# LARS.net
KiCad netlist of a schematic drawn in EAGLE
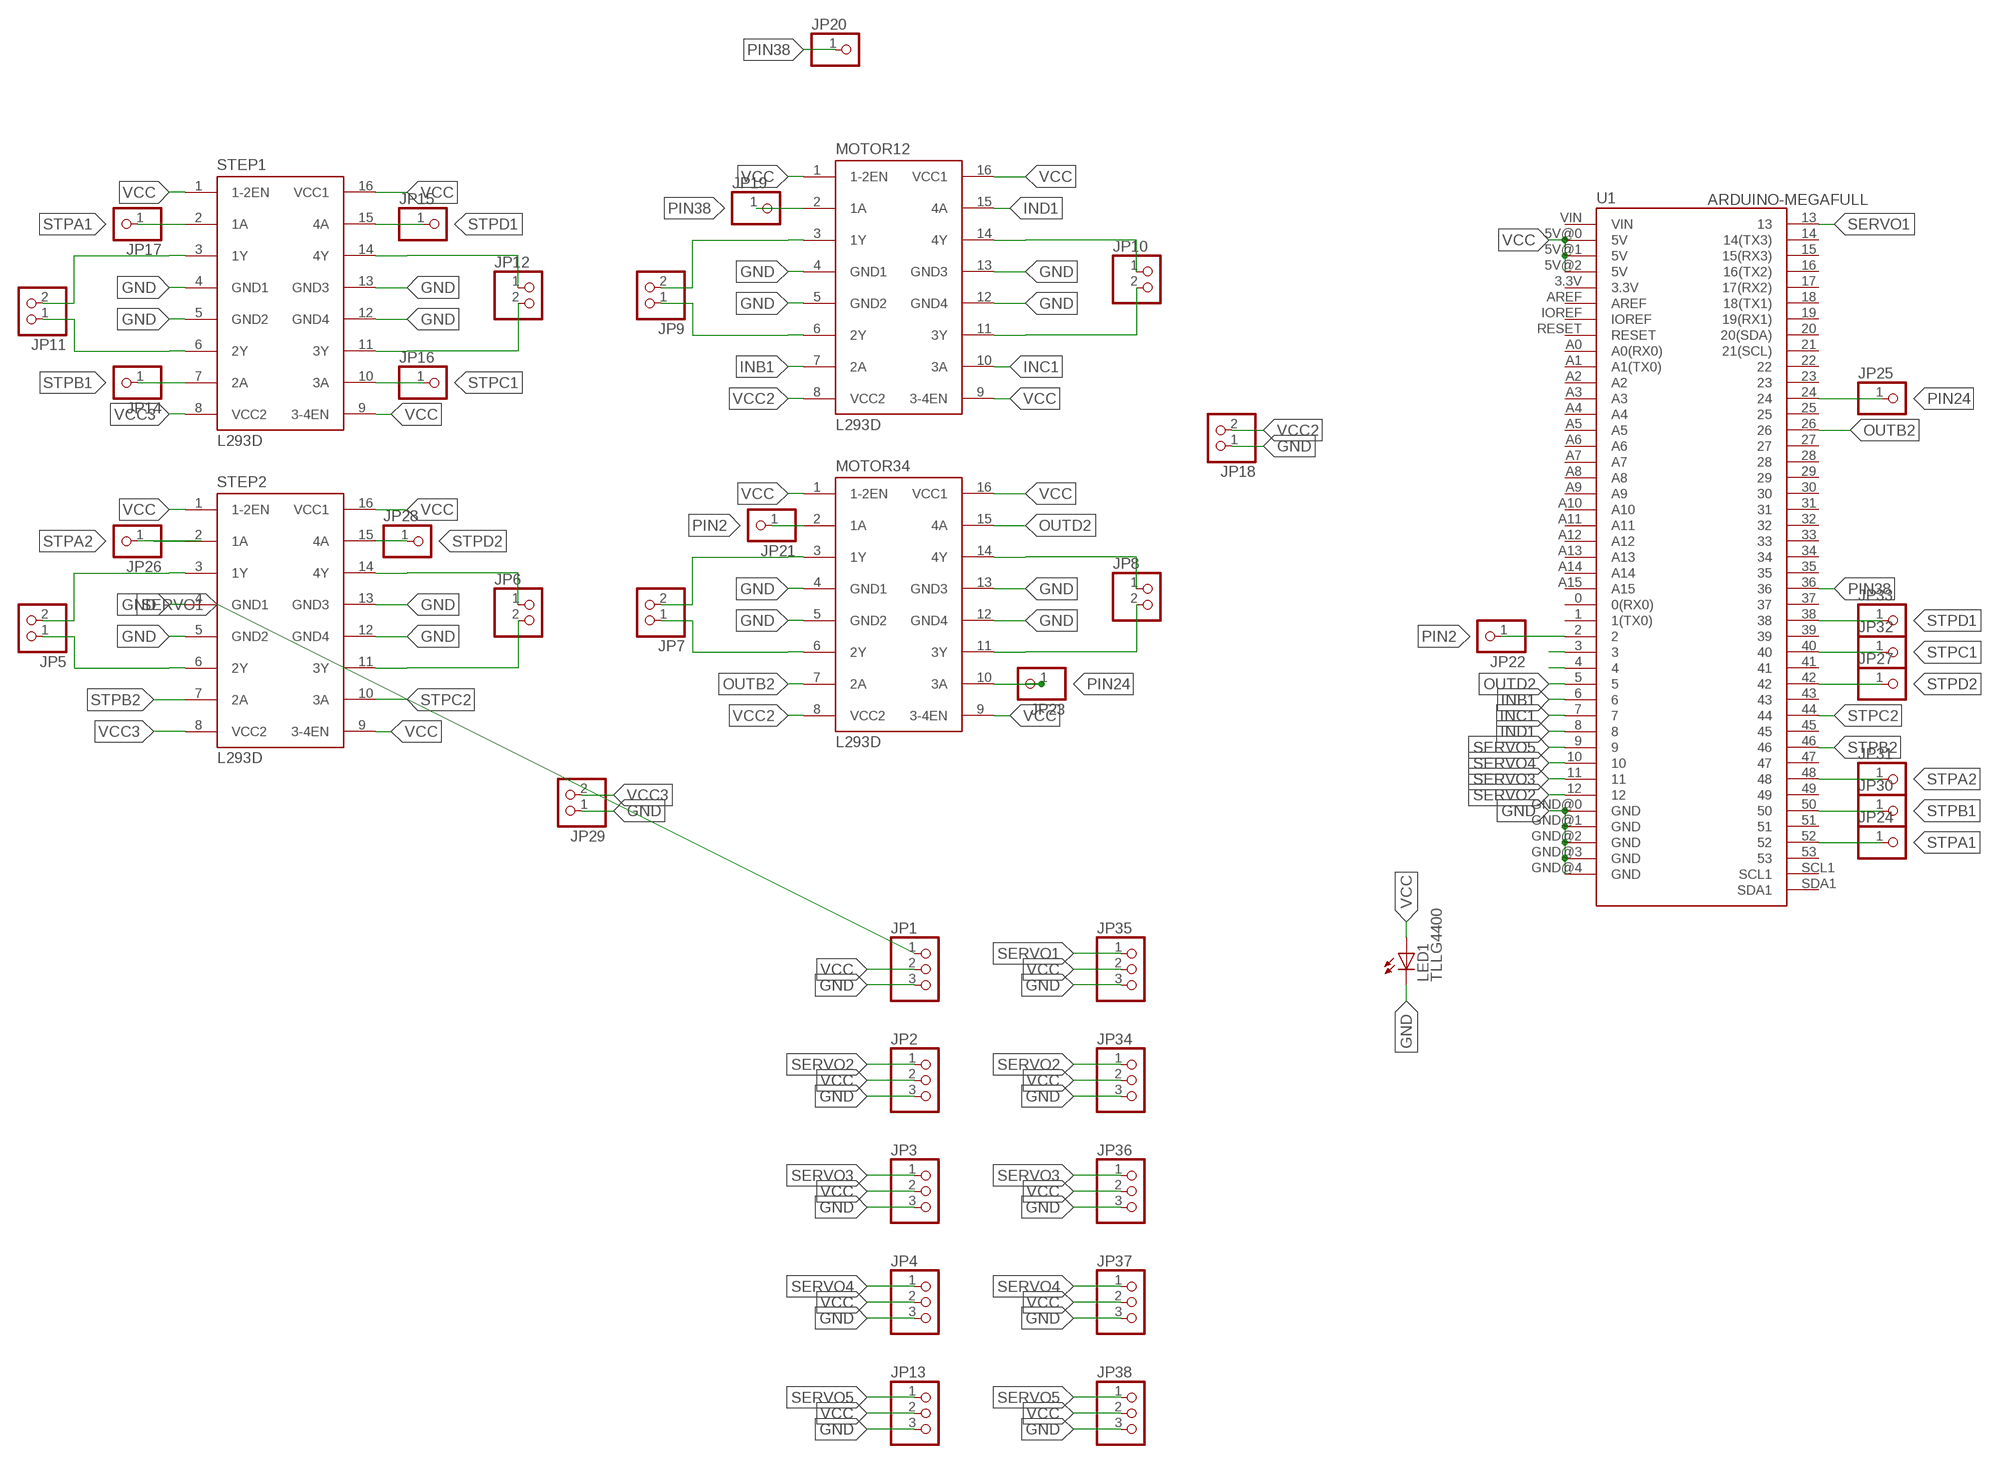
[diagram p0: schematic, sheet 1]

(export (version "E")
  (design (tool "Eeschema 10.0.6"))
  (components
    (comp (ref "JP1")
      (value "PINHD-1X3")
      (footprint "eagle-import:1X03")
      (libsource (lib "eagle-import") (part "PINHD-1X3"))
    )
    (comp (ref "JP2")
      (value "PINHD-1X3")
      (footprint "eagle-import:1X03")
      (libsource (lib "eagle-import") (part "PINHD-1X3"))
    )
    (comp (ref "JP3")
      (value "PINHD-1X3")
      (footprint "eagle-import:1X03")
      (libsource (lib "eagle-import") (part "PINHD-1X3"))
    )
    (comp (ref "JP4")
      (value "PINHD-1X3")
      (footprint "eagle-import:1X03")
      (libsource (lib "eagle-import") (part "PINHD-1X3"))
    )
    (comp (ref "JP5")
      (value "PINHD-1X2")
      (footprint "eagle-import:1X02")
      (libsource (lib "eagle-import") (part "PINHD-1X2"))
    )
    (comp (ref "JP6")
      (value "PINHD-1X2")
      (footprint "eagle-import:1X02")
      (libsource (lib "eagle-import") (part "PINHD-1X2"))
    )
    (comp (ref "JP7")
      (value "PINHD-1X2")
      (footprint "eagle-import:1X02")
      (libsource (lib "eagle-import") (part "PINHD-1X2"))
    )
    (comp (ref "JP8")
      (value "PINHD-1X2")
      (footprint "eagle-import:1X02")
      (libsource (lib "eagle-import") (part "PINHD-1X2"))
    )
    (comp (ref "JP9")
      (value "PINHD-1X2")
      (footprint "eagle-import:1X02")
      (libsource (lib "eagle-import") (part "PINHD-1X2"))
    )
    (comp (ref "JP10")
      (value "PINHD-1X2")
      (footprint "eagle-import:1X02")
      (libsource (lib "eagle-import") (part "PINHD-1X2"))
    )
    (comp (ref "JP11")
      (value "PINHD-1X2")
      (footprint "eagle-import:1X02")
      (libsource (lib "eagle-import") (part "PINHD-1X2"))
    )
    (comp (ref "JP12")
      (value "PINHD-1X2")
      (footprint "eagle-import:1X02")
      (libsource (lib "eagle-import") (part "PINHD-1X2"))
    )
    (comp (ref "JP13")
      (value "PINHD-1X3")
      (footprint "eagle-import:1X03")
      (libsource (lib "eagle-import") (part "PINHD-1X3"))
    )
    (comp (ref "JP14")
      (value "PINHD-1X1")
      (footprint "eagle-import:1X01")
      (libsource (lib "eagle-import") (part "PINHD-1X1"))
    )
    (comp (ref "JP15")
      (value "PINHD-1X1")
      (footprint "eagle-import:1X01")
      (libsource (lib "eagle-import") (part "PINHD-1X1"))
    )
    (comp (ref "JP16")
      (value "PINHD-1X1")
      (footprint "eagle-import:1X01")
      (libsource (lib "eagle-import") (part "PINHD-1X1"))
    )
    (comp (ref "JP17")
      (value "PINHD-1X1")
      (footprint "eagle-import:1X01")
      (libsource (lib "eagle-import") (part "PINHD-1X1"))
    )
    (comp (ref "JP18")
      (value "PINHD-1X2")
      (footprint "eagle-import:1X02")
      (libsource (lib "eagle-import") (part "PINHD-1X2"))
    )
    (comp (ref "JP19")
      (value "PINHD-1X1")
      (footprint "eagle-import:1X01")
      (libsource (lib "eagle-import") (part "PINHD-1X1"))
    )
    (comp (ref "JP20")
      (value "PINHD-1X1")
      (footprint "eagle-import:1X01")
      (libsource (lib "eagle-import") (part "PINHD-1X1"))
    )
    (comp (ref "JP21")
      (value "PINHD-1X1")
      (footprint "eagle-import:1X01")
      (libsource (lib "eagle-import") (part "PINHD-1X1"))
    )
    (comp (ref "JP22")
      (value "PINHD-1X1")
      (footprint "eagle-import:1X01")
      (libsource (lib "eagle-import") (part "PINHD-1X1"))
    )
    (comp (ref "JP23")
      (value "PINHD-1X1")
      (footprint "eagle-import:1X01")
      (libsource (lib "eagle-import") (part "PINHD-1X1"))
    )
    (comp (ref "JP24")
      (value "PINHD-1X1")
      (footprint "eagle-import:1X01")
      (libsource (lib "eagle-import") (part "PINHD-1X1"))
    )
    (comp (ref "JP25")
      (value "PINHD-1X1")
      (footprint "eagle-import:1X01")
      (libsource (lib "eagle-import") (part "PINHD-1X1"))
    )
    (comp (ref "JP26")
      (value "PINHD-1X1")
      (footprint "eagle-import:1X01")
      (libsource (lib "eagle-import") (part "PINHD-1X1"))
    )
    (comp (ref "JP27")
      (value "PINHD-1X1")
      (footprint "eagle-import:1X01")
      (libsource (lib "eagle-import") (part "PINHD-1X1"))
    )
    (comp (ref "JP28")
      (value "PINHD-1X1")
      (footprint "eagle-import:1X01")
      (libsource (lib "eagle-import") (part "PINHD-1X1"))
    )
    (comp (ref "JP29")
      (value "PINHD-1X2")
      (footprint "eagle-import:1X02")
      (libsource (lib "eagle-import") (part "PINHD-1X2"))
    )
    (comp (ref "JP30")
      (value "PINHD-1X1")
      (footprint "eagle-import:1X01")
      (libsource (lib "eagle-import") (part "PINHD-1X1"))
    )
    (comp (ref "JP31")
      (value "PINHD-1X1")
      (footprint "eagle-import:1X01")
      (libsource (lib "eagle-import") (part "PINHD-1X1"))
    )
    (comp (ref "JP32")
      (value "PINHD-1X1")
      (footprint "eagle-import:1X01")
      (libsource (lib "eagle-import") (part "PINHD-1X1"))
    )
    (comp (ref "JP33")
      (value "PINHD-1X1")
      (footprint "eagle-import:1X01")
      (libsource (lib "eagle-import") (part "PINHD-1X1"))
    )
    (comp (ref "JP34")
      (value "PINHD-1X3")
      (footprint "eagle-import:1X03")
      (libsource (lib "eagle-import") (part "PINHD-1X3"))
    )
    (comp (ref "JP35")
      (value "PINHD-1X3")
      (footprint "eagle-import:1X03")
      (libsource (lib "eagle-import") (part "PINHD-1X3"))
    )
    (comp (ref "JP36")
      (value "PINHD-1X3")
      (footprint "eagle-import:1X03")
      (libsource (lib "eagle-import") (part "PINHD-1X3"))
    )
    (comp (ref "JP37")
      (value "PINHD-1X3")
      (footprint "eagle-import:1X03")
      (libsource (lib "eagle-import") (part "PINHD-1X3"))
    )
    (comp (ref "JP38")
      (value "PINHD-1X3")
      (footprint "eagle-import:1X03")
      (libsource (lib "eagle-import") (part "PINHD-1X3"))
    )
    (comp (ref "LED1")
      (value "TLLG4400")
      (footprint "eagle-import:LED3MM")
      (fields (field (name "MF") "VISHAY SEMICONDUCTOR"))
      (libsource (lib "eagle-import") (part "TLLG4400"))
    )
    (comp (ref "MOTOR12")
      (value "L293D")
      (footprint "eagle-import:DIL16")
      (libsource (lib "eagle-import") (part "L293D"))
    )
    (comp (ref "MOTOR34")
      (value "L293D")
      (footprint "eagle-import:DIL16")
      (libsource (lib "eagle-import") (part "L293D"))
    )
    (comp (ref "STEP1")
      (value "L293D")
      (footprint "eagle-import:DIL16")
      (libsource (lib "eagle-import") (part "L293D"))
    )
    (comp (ref "STEP2")
      (value "L293D")
      (footprint "eagle-import:DIL16")
      (libsource (lib "eagle-import") (part "L293D"))
    )
    (comp (ref "U1")
      (value "ARDUINO-MEGAFULL")
      (footprint "eagle-import:ARDUINO_MEGA")
      (libsource (lib "eagle-import") (part "ARDUINO-MEGAFULL"))
    )
  )
  (nets
    (net (code "1") (name "GND") (class "Default")
      (node (ref "JP1") (pin "3") (pinfunction "3_3") (pintype "passive"))
      (node (ref "JP13") (pin "3") (pinfunction "3_3") (pintype "passive"))
      (node (ref "JP18") (pin "1") (pinfunction "1_1") (pintype "passive"))
      (node (ref "JP2") (pin "3") (pinfunction "3_3") (pintype "passive"))
      (node (ref "JP29") (pin "1") (pinfunction "1_1") (pintype "passive"))
      (node (ref "JP3") (pin "3") (pinfunction "3_3") (pintype "passive"))
      (node (ref "JP34") (pin "3") (pinfunction "3_3") (pintype "passive"))
      (node (ref "JP35") (pin "3") (pinfunction "3_3") (pintype "passive"))
      (node (ref "JP36") (pin "3") (pinfunction "3_3") (pintype "passive"))
      (node (ref "JP37") (pin "3") (pinfunction "3_3") (pintype "passive"))
      (node (ref "JP38") (pin "3") (pinfunction "3_3") (pintype "passive"))
      (node (ref "JP4") (pin "3") (pinfunction "3_3") (pintype "passive"))
      (node (ref "LED1") (pin "K") (pinfunction "C_K") (pintype "passive"))
      (node (ref "MOTOR12") (pin "12") (pinfunction "GND4_12") (pintype "power_in"))
      (node (ref "MOTOR12") (pin "13") (pinfunction "GND3_13") (pintype "power_in"))
      (node (ref "MOTOR12") (pin "4") (pinfunction "GND1_4") (pintype "power_in"))
      (node (ref "MOTOR12") (pin "5") (pinfunction "GND2_5") (pintype "power_in"))
      (node (ref "MOTOR34") (pin "12") (pinfunction "GND4_12") (pintype "power_in"))
      (node (ref "MOTOR34") (pin "13") (pinfunction "GND3_13") (pintype "power_in"))
      (node (ref "MOTOR34") (pin "4") (pinfunction "GND1_4") (pintype "power_in"))
      (node (ref "MOTOR34") (pin "5") (pinfunction "GND2_5") (pintype "power_in"))
      (node (ref "STEP1") (pin "12") (pinfunction "GND4_12") (pintype "power_in"))
      (node (ref "STEP1") (pin "13") (pinfunction "GND3_13") (pintype "power_in"))
      (node (ref "STEP1") (pin "4") (pinfunction "GND1_4") (pintype "power_in"))
      (node (ref "STEP1") (pin "5") (pinfunction "GND2_5") (pintype "power_in"))
      (node (ref "STEP2") (pin "12") (pinfunction "GND4_12") (pintype "power_in"))
      (node (ref "STEP2") (pin "13") (pinfunction "GND3_13") (pintype "power_in"))
      (node (ref "STEP2") (pin "4") (pinfunction "GND1_4") (pintype "power_in"))
      (node (ref "STEP2") (pin "5") (pinfunction "GND2_5") (pintype "power_in"))
      (node (ref "U1") (pin "GND@0") (pinfunction "GND_GND@0") (pintype "bidirectional"))
      (node (ref "U1") (pin "GND@1") (pinfunction "GND_GND@1") (pintype "bidirectional"))
      (node (ref "U1") (pin "GND@2") (pinfunction "GND_GND@2") (pintype "bidirectional"))
      (node (ref "U1") (pin "GND@3") (pinfunction "GND_GND@3") (pintype "bidirectional"))
      (node (ref "U1") (pin "GND@4") (pinfunction "GND_GND@4") (pintype "bidirectional"))
    )
    (net (code "2") (name "INB1") (class "Default")
      (node (ref "MOTOR12") (pin "7") (pinfunction "2A_7") (pintype "input"))
      (node (ref "U1") (pin "6") (pinfunction "6_6") (pintype "bidirectional"))
    )
    (net (code "3") (name "INC1") (class "Default")
      (node (ref "MOTOR12") (pin "10") (pinfunction "3A_10") (pintype "input"))
      (node (ref "U1") (pin "7") (pinfunction "7_7") (pintype "bidirectional"))
    )
    (net (code "4") (name "IND1") (class "Default")
      (node (ref "MOTOR12") (pin "15") (pinfunction "4A_15") (pintype "input"))
      (node (ref "U1") (pin "8") (pinfunction "8_8") (pintype "bidirectional"))
    )
    (net (code "5") (name "Net-(MOTOR12-1Y)") (class "Default")
      (node (ref "JP9") (pin "2") (pinfunction "2_2") (pintype "passive"))
      (node (ref "MOTOR12") (pin "3") (pinfunction "1Y_3") (pintype "output"))
    )
    (net (code "6") (name "Net-(MOTOR12-2Y)") (class "Default")
      (node (ref "JP9") (pin "1") (pinfunction "1_1") (pintype "passive"))
      (node (ref "MOTOR12") (pin "6") (pinfunction "2Y_6") (pintype "output"))
    )
    (net (code "7") (name "Net-(MOTOR12-3Y)") (class "Default")
      (node (ref "JP10") (pin "2") (pinfunction "2_2") (pintype "passive"))
      (node (ref "MOTOR12") (pin "11") (pinfunction "3Y_11") (pintype "output"))
    )
    (net (code "8") (name "Net-(MOTOR12-4Y)") (class "Default")
      (node (ref "JP10") (pin "1") (pinfunction "1_1") (pintype "passive"))
      (node (ref "MOTOR12") (pin "14") (pinfunction "4Y_14") (pintype "output"))
    )
    (net (code "9") (name "Net-(MOTOR34-1Y)") (class "Default")
      (node (ref "JP7") (pin "2") (pinfunction "2_2") (pintype "passive"))
      (node (ref "MOTOR34") (pin "3") (pinfunction "1Y_3") (pintype "output"))
    )
    (net (code "10") (name "Net-(MOTOR34-2Y)") (class "Default")
      (node (ref "JP7") (pin "1") (pinfunction "1_1") (pintype "passive"))
      (node (ref "MOTOR34") (pin "6") (pinfunction "2Y_6") (pintype "output"))
    )
    (net (code "11") (name "Net-(MOTOR34-3Y)") (class "Default")
      (node (ref "JP8") (pin "2") (pinfunction "2_2") (pintype "passive"))
      (node (ref "MOTOR34") (pin "11") (pinfunction "3Y_11") (pintype "output"))
    )
    (net (code "12") (name "Net-(MOTOR34-4Y)") (class "Default")
      (node (ref "JP8") (pin "1") (pinfunction "1_1") (pintype "passive"))
      (node (ref "MOTOR34") (pin "14") (pinfunction "4Y_14") (pintype "output"))
    )
    (net (code "13") (name "Net-(STEP1-1Y)") (class "Default")
      (node (ref "JP11") (pin "2") (pinfunction "2_2") (pintype "passive"))
      (node (ref "STEP1") (pin "3") (pinfunction "1Y_3") (pintype "output"))
    )
    (net (code "14") (name "Net-(STEP1-2Y)") (class "Default")
      (node (ref "JP11") (pin "1") (pinfunction "1_1") (pintype "passive"))
      (node (ref "STEP1") (pin "6") (pinfunction "2Y_6") (pintype "output"))
    )
    (net (code "15") (name "Net-(STEP1-3Y)") (class "Default")
      (node (ref "JP12") (pin "2") (pinfunction "2_2") (pintype "passive"))
      (node (ref "STEP1") (pin "11") (pinfunction "3Y_11") (pintype "output"))
    )
    (net (code "16") (name "Net-(STEP1-4Y)") (class "Default")
      (node (ref "JP12") (pin "1") (pinfunction "1_1") (pintype "passive"))
      (node (ref "STEP1") (pin "14") (pinfunction "4Y_14") (pintype "output"))
    )
    (net (code "17") (name "Net-(STEP2-1Y)") (class "Default")
      (node (ref "JP5") (pin "2") (pinfunction "2_2") (pintype "passive"))
      (node (ref "STEP2") (pin "3") (pinfunction "1Y_3") (pintype "output"))
    )
    (net (code "18") (name "Net-(STEP2-2Y)") (class "Default")
      (node (ref "JP5") (pin "1") (pinfunction "1_1") (pintype "passive"))
      (node (ref "STEP2") (pin "6") (pinfunction "2Y_6") (pintype "output"))
    )
    (net (code "19") (name "Net-(STEP2-3Y)") (class "Default")
      (node (ref "JP6") (pin "2") (pinfunction "2_2") (pintype "passive"))
      (node (ref "STEP2") (pin "11") (pinfunction "3Y_11") (pintype "output"))
    )
    (net (code "20") (name "Net-(STEP2-4Y)") (class "Default")
      (node (ref "JP6") (pin "1") (pinfunction "1_1") (pintype "passive"))
      (node (ref "STEP2") (pin "14") (pinfunction "4Y_14") (pintype "output"))
    )
    (net (code "21") (name "OUTB2") (class "Default")
      (node (ref "MOTOR34") (pin "7") (pinfunction "2A_7") (pintype "input"))
      (node (ref "U1") (pin "26") (pinfunction "26_26") (pintype "bidirectional"))
    )
    (net (code "22") (name "OUTD2") (class "Default")
      (node (ref "MOTOR34") (pin "15") (pinfunction "4A_15") (pintype "input"))
      (node (ref "U1") (pin "5") (pinfunction "5_5") (pintype "bidirectional"))
    )
    (net (code "23") (name "PIN2") (class "Default")
      (node (ref "JP21") (pin "1") (pinfunction "1_1") (pintype "passive"))
      (node (ref "JP22") (pin "1") (pinfunction "1_1") (pintype "passive"))
      (node (ref "MOTOR34") (pin "2") (pinfunction "1A_2") (pintype "input"))
      (node (ref "U1") (pin "2") (pinfunction "2_2") (pintype "bidirectional"))
    )
    (net (code "24") (name "PIN24") (class "Default")
      (node (ref "JP23") (pin "1") (pinfunction "1_1") (pintype "passive"))
      (node (ref "JP25") (pin "1") (pinfunction "1_1") (pintype "passive"))
      (node (ref "MOTOR34") (pin "10") (pinfunction "3A_10") (pintype "input"))
      (node (ref "U1") (pin "24") (pinfunction "24_24") (pintype "bidirectional"))
    )
    (net (code "25") (name "PIN38") (class "Default")
      (node (ref "JP19") (pin "1") (pinfunction "1_1") (pintype "passive"))
      (node (ref "JP20") (pin "1") (pinfunction "1_1") (pintype "passive"))
      (node (ref "MOTOR12") (pin "2") (pinfunction "1A_2") (pintype "input"))
      (node (ref "U1") (pin "36") (pinfunction "36_36") (pintype "bidirectional"))
    )
    (net (code "26") (name "SERVO1") (class "Default")
      (node (ref "JP1") (pin "1") (pinfunction "1_1") (pintype "passive"))
      (node (ref "JP35") (pin "1") (pinfunction "1_1") (pintype "passive"))
      (node (ref "U1") (pin "13") (pinfunction "13_13") (pintype "bidirectional"))
    )
    (net (code "27") (name "SERVO2") (class "Default")
      (node (ref "JP2") (pin "1") (pinfunction "1_1") (pintype "passive"))
      (node (ref "JP34") (pin "1") (pinfunction "1_1") (pintype "passive"))
      (node (ref "U1") (pin "12") (pinfunction "12_12") (pintype "bidirectional"))
    )
    (net (code "28") (name "SERVO3") (class "Default")
      (node (ref "JP3") (pin "1") (pinfunction "1_1") (pintype "passive"))
      (node (ref "JP36") (pin "1") (pinfunction "1_1") (pintype "passive"))
      (node (ref "U1") (pin "11") (pinfunction "11_11") (pintype "bidirectional"))
    )
    (net (code "29") (name "SERVO4") (class "Default")
      (node (ref "JP37") (pin "1") (pinfunction "1_1") (pintype "passive"))
      (node (ref "JP4") (pin "1") (pinfunction "1_1") (pintype "passive"))
      (node (ref "U1") (pin "10") (pinfunction "10_10") (pintype "bidirectional"))
    )
    (net (code "30") (name "SERVO5") (class "Default")
      (node (ref "JP13") (pin "1") (pinfunction "1_1") (pintype "passive"))
      (node (ref "JP38") (pin "1") (pinfunction "1_1") (pintype "passive"))
      (node (ref "U1") (pin "9") (pinfunction "9_9") (pintype "bidirectional"))
    )
    (net (code "31") (name "STPA1") (class "Default")
      (node (ref "JP17") (pin "1") (pinfunction "1_1") (pintype "passive"))
      (node (ref "JP24") (pin "1") (pinfunction "1_1") (pintype "passive"))
      (node (ref "STEP1") (pin "2") (pinfunction "1A_2") (pintype "input"))
      (node (ref "U1") (pin "52") (pinfunction "52_52") (pintype "bidirectional"))
    )
    (net (code "32") (name "STPA2") (class "Default")
      (node (ref "JP26") (pin "1") (pinfunction "1_1") (pintype "passive"))
      (node (ref "JP31") (pin "1") (pinfunction "1_1") (pintype "passive"))
      (node (ref "STEP2") (pin "2") (pinfunction "1A_2") (pintype "input"))
      (node (ref "U1") (pin "48") (pinfunction "48_48") (pintype "bidirectional"))
    )
    (net (code "33") (name "STPB1") (class "Default")
      (node (ref "JP14") (pin "1") (pinfunction "1_1") (pintype "passive"))
      (node (ref "JP30") (pin "1") (pinfunction "1_1") (pintype "passive"))
      (node (ref "STEP1") (pin "7") (pinfunction "2A_7") (pintype "input"))
      (node (ref "U1") (pin "50") (pinfunction "50_50") (pintype "bidirectional"))
    )
    (net (code "34") (name "STPB2") (class "Default")
      (node (ref "STEP2") (pin "7") (pinfunction "2A_7") (pintype "input"))
      (node (ref "U1") (pin "46") (pinfunction "46_46") (pintype "bidirectional"))
    )
    (net (code "35") (name "STPC1") (class "Default")
      (node (ref "JP16") (pin "1") (pinfunction "1_1") (pintype "passive"))
      (node (ref "JP32") (pin "1") (pinfunction "1_1") (pintype "passive"))
      (node (ref "STEP1") (pin "10") (pinfunction "3A_10") (pintype "input"))
      (node (ref "U1") (pin "40") (pinfunction "40_40") (pintype "bidirectional"))
    )
    (net (code "36") (name "STPC2") (class "Default")
      (node (ref "STEP2") (pin "10") (pinfunction "3A_10") (pintype "input"))
      (node (ref "U1") (pin "44") (pinfunction "44_44") (pintype "bidirectional"))
    )
    (net (code "37") (name "STPD1") (class "Default")
      (node (ref "JP15") (pin "1") (pinfunction "1_1") (pintype "passive"))
      (node (ref "JP33") (pin "1") (pinfunction "1_1") (pintype "passive"))
      (node (ref "STEP1") (pin "15") (pinfunction "4A_15") (pintype "input"))
      (node (ref "U1") (pin "38") (pinfunction "38_38") (pintype "bidirectional"))
    )
    (net (code "38") (name "STPD2") (class "Default")
      (node (ref "JP27") (pin "1") (pinfunction "1_1") (pintype "passive"))
      (node (ref "JP28") (pin "1") (pinfunction "1_1") (pintype "passive"))
      (node (ref "STEP2") (pin "15") (pinfunction "4A_15") (pintype "input"))
      (node (ref "U1") (pin "42") (pinfunction "42_42") (pintype "bidirectional"))
    )
    (net (code "39") (name "VCC") (class "Default")
      (node (ref "JP1") (pin "2") (pinfunction "2_2") (pintype "passive"))
      (node (ref "JP13") (pin "2") (pinfunction "2_2") (pintype "passive"))
      (node (ref "JP2") (pin "2") (pinfunction "2_2") (pintype "passive"))
      (node (ref "JP3") (pin "2") (pinfunction "2_2") (pintype "passive"))
      (node (ref "JP34") (pin "2") (pinfunction "2_2") (pintype "passive"))
      (node (ref "JP35") (pin "2") (pinfunction "2_2") (pintype "passive"))
      (node (ref "JP36") (pin "2") (pinfunction "2_2") (pintype "passive"))
      (node (ref "JP37") (pin "2") (pinfunction "2_2") (pintype "passive"))
      (node (ref "JP38") (pin "2") (pinfunction "2_2") (pintype "passive"))
      (node (ref "JP4") (pin "2") (pinfunction "2_2") (pintype "passive"))
      (node (ref "LED1") (pin "A") (pinfunction "A_A") (pintype "passive"))
      (node (ref "MOTOR12") (pin "1") (pinfunction "1-2EN_1") (pintype "input"))
      (node (ref "MOTOR12") (pin "16") (pinfunction "VCC1_16") (pintype "power_in"))
      (node (ref "MOTOR12") (pin "9") (pinfunction "3-4EN_9") (pintype "input"))
      (node (ref "MOTOR34") (pin "1") (pinfunction "1-2EN_1") (pintype "input"))
      (node (ref "MOTOR34") (pin "16") (pinfunction "VCC1_16") (pintype "power_in"))
      (node (ref "MOTOR34") (pin "9") (pinfunction "3-4EN_9") (pintype "input"))
      (node (ref "STEP1") (pin "1") (pinfunction "1-2EN_1") (pintype "input"))
      (node (ref "STEP1") (pin "16") (pinfunction "VCC1_16") (pintype "power_in"))
      (node (ref "STEP1") (pin "9") (pinfunction "3-4EN_9") (pintype "input"))
      (node (ref "STEP2") (pin "1") (pinfunction "1-2EN_1") (pintype "input"))
      (node (ref "STEP2") (pin "16") (pinfunction "VCC1_16") (pintype "power_in"))
      (node (ref "STEP2") (pin "9") (pinfunction "3-4EN_9") (pintype "input"))
      (node (ref "U1") (pin "5V@0") (pinfunction "5V_5V@0") (pintype "bidirectional"))
      (node (ref "U1") (pin "5V@1") (pinfunction "5V_5V@1") (pintype "bidirectional"))
      (node (ref "U1") (pin "5V@2") (pinfunction "5V_5V@2") (pintype "bidirectional"))
    )
    (net (code "40") (name "VCC2") (class "Default")
      (node (ref "JP18") (pin "2") (pinfunction "2_2") (pintype "passive"))
      (node (ref "MOTOR12") (pin "8") (pinfunction "VCC2_8") (pintype "power_in"))
      (node (ref "MOTOR34") (pin "8") (pinfunction "VCC2_8") (pintype "power_in"))
    )
    (net (code "41") (name "VCC3") (class "Default")
      (node (ref "JP29") (pin "2") (pinfunction "2_2") (pintype "passive"))
      (node (ref "STEP1") (pin "8") (pinfunction "VCC2_8") (pintype "power_in"))
      (node (ref "STEP2") (pin "8") (pinfunction "VCC2_8") (pintype "power_in"))
    )
    (net (code "42") (name "unconnected-(U1-0(RX0)-Pad0)") (class "Default")
      (node (ref "U1") (pin "0") (pinfunction "0(RX0)_0") (pintype "bidirectional"))
    )
    (net (code "43") (name "unconnected-(U1-1(TX0)-Pad1)") (class "Default")
      (node (ref "U1") (pin "1") (pinfunction "1(TX0)_1") (pintype "bidirectional"))
    )
    (net (code "44") (name "unconnected-(U1-14(TX3)-Pad14)") (class "Default")
      (node (ref "U1") (pin "14") (pinfunction "14(TX3)_14") (pintype "bidirectional"))
    )
    (net (code "45") (name "unconnected-(U1-15(RX3)-Pad15)") (class "Default")
      (node (ref "U1") (pin "15") (pinfunction "15(RX3)_15") (pintype "bidirectional"))
    )
    (net (code "46") (name "unconnected-(U1-16(TX2)-Pad16)") (class "Default")
      (node (ref "U1") (pin "16") (pinfunction "16(TX2)_16") (pintype "bidirectional"))
    )
    (net (code "47") (name "unconnected-(U1-17(RX2)-Pad17)") (class "Default")
      (node (ref "U1") (pin "17") (pinfunction "17(RX2)_17") (pintype "bidirectional"))
    )
    (net (code "48") (name "unconnected-(U1-18(TX1)-Pad18)") (class "Default")
      (node (ref "U1") (pin "18") (pinfunction "18(TX1)_18") (pintype "bidirectional"))
    )
    (net (code "49") (name "unconnected-(U1-19(RX1)-Pad19)") (class "Default")
      (node (ref "U1") (pin "19") (pinfunction "19(RX1)_19") (pintype "bidirectional"))
    )
    (net (code "50") (name "unconnected-(U1-20(SDA)-Pad20)") (class "Default")
      (node (ref "U1") (pin "20") (pinfunction "20(SDA)_20") (pintype "bidirectional"))
    )
    (net (code "51") (name "unconnected-(U1-21(SCL)-Pad21)") (class "Default")
      (node (ref "U1") (pin "21") (pinfunction "21(SCL)_21") (pintype "bidirectional"))
    )
    (net (code "52") (name "unconnected-(U1-A0(RX0)-PadA0)") (class "Default")
      (node (ref "U1") (pin "A0") (pinfunction "A0(RX0)_A0") (pintype "bidirectional"))
    )
    (net (code "53") (name "unconnected-(U1-A1(TX0)-PadA1)") (class "Default")
      (node (ref "U1") (pin "A1") (pinfunction "A1(TX0)_A1") (pintype "bidirectional"))
    )
    (net (code "54") (name "unconnected-(U1-Pad3)") (class "Default")
      (node (ref "U1") (pin "3") (pinfunction "3_3") (pintype "bidirectional"))
    )
    (net (code "55") (name "unconnected-(U1-Pad3.3V)") (class "Default")
      (node (ref "U1") (pin "3.3V") (pinfunction "3.3V_3.3V") (pintype "bidirectional"))
    )
    (net (code "56") (name "unconnected-(U1-Pad4)") (class "Default")
      (node (ref "U1") (pin "4") (pinfunction "4_4") (pintype "bidirectional"))
    )
    (net (code "57") (name "unconnected-(U1-Pad22)") (class "Default")
      (node (ref "U1") (pin "22") (pinfunction "22_22") (pintype "bidirectional"))
    )
    (net (code "58") (name "unconnected-(U1-Pad23)") (class "Default")
      (node (ref "U1") (pin "23") (pinfunction "23_23") (pintype "bidirectional"))
    )
    (net (code "59") (name "unconnected-(U1-Pad25)") (class "Default")
      (node (ref "U1") (pin "25") (pinfunction "25_25") (pintype "bidirectional"))
    )
    (net (code "60") (name "unconnected-(U1-Pad27)") (class "Default")
      (node (ref "U1") (pin "27") (pinfunction "27_27") (pintype "bidirectional"))
    )
    (net (code "61") (name "unconnected-(U1-Pad28)") (class "Default")
      (node (ref "U1") (pin "28") (pinfunction "28_28") (pintype "bidirectional"))
    )
    (net (code "62") (name "unconnected-(U1-Pad29)") (class "Default")
      (node (ref "U1") (pin "29") (pinfunction "29_29") (pintype "bidirectional"))
    )
    (net (code "63") (name "unconnected-(U1-Pad30)") (class "Default")
      (node (ref "U1") (pin "30") (pinfunction "30_30") (pintype "bidirectional"))
    )
    (net (code "64") (name "unconnected-(U1-Pad31)") (class "Default")
      (node (ref "U1") (pin "31") (pinfunction "31_31") (pintype "bidirectional"))
    )
    (net (code "65") (name "unconnected-(U1-Pad32)") (class "Default")
      (node (ref "U1") (pin "32") (pinfunction "32_32") (pintype "bidirectional"))
    )
    (net (code "66") (name "unconnected-(U1-Pad33)") (class "Default")
      (node (ref "U1") (pin "33") (pinfunction "33_33") (pintype "bidirectional"))
    )
    (net (code "67") (name "unconnected-(U1-Pad34)") (class "Default")
      (node (ref "U1") (pin "34") (pinfunction "34_34") (pintype "bidirectional"))
    )
    (net (code "68") (name "unconnected-(U1-Pad35)") (class "Default")
      (node (ref "U1") (pin "35") (pinfunction "35_35") (pintype "bidirectional"))
    )
    (net (code "69") (name "unconnected-(U1-Pad37)") (class "Default")
      (node (ref "U1") (pin "37") (pinfunction "37_37") (pintype "bidirectional"))
    )
    (net (code "70") (name "unconnected-(U1-Pad39)") (class "Default")
      (node (ref "U1") (pin "39") (pinfunction "39_39") (pintype "bidirectional"))
    )
    (net (code "71") (name "unconnected-(U1-Pad41)") (class "Default")
      (node (ref "U1") (pin "41") (pinfunction "41_41") (pintype "bidirectional"))
    )
    (net (code "72") (name "unconnected-(U1-Pad43)") (class "Default")
      (node (ref "U1") (pin "43") (pinfunction "43_43") (pintype "bidirectional"))
    )
    (net (code "73") (name "unconnected-(U1-Pad45)") (class "Default")
      (node (ref "U1") (pin "45") (pinfunction "45_45") (pintype "bidirectional"))
    )
    (net (code "74") (name "unconnected-(U1-Pad47)") (class "Default")
      (node (ref "U1") (pin "47") (pinfunction "47_47") (pintype "bidirectional"))
    )
    (net (code "75") (name "unconnected-(U1-Pad49)") (class "Default")
      (node (ref "U1") (pin "49") (pinfunction "49_49") (pintype "bidirectional"))
    )
    (net (code "76") (name "unconnected-(U1-Pad51)") (class "Default")
      (node (ref "U1") (pin "51") (pinfunction "51_51") (pintype "bidirectional"))
    )
    (net (code "77") (name "unconnected-(U1-Pad53)") (class "Default")
      (node (ref "U1") (pin "53") (pinfunction "53_53") (pintype "bidirectional"))
    )
    (net (code "78") (name "unconnected-(U1-PadA2)") (class "Default")
      (node (ref "U1") (pin "A2") (pinfunction "A2_A2") (pintype "bidirectional"))
    )
    (net (code "79") (name "unconnected-(U1-PadA3)") (class "Default")
      (node (ref "U1") (pin "A3") (pinfunction "A3_A3") (pintype "bidirectional"))
    )
    (net (code "80") (name "unconnected-(U1-PadA4)") (class "Default")
      (node (ref "U1") (pin "A4") (pinfunction "A4_A4") (pintype "bidirectional"))
    )
    (net (code "81") (name "unconnected-(U1-PadA5)") (class "Default")
      (node (ref "U1") (pin "A5") (pinfunction "A5_A5") (pintype "bidirectional"))
    )
    (net (code "82") (name "unconnected-(U1-PadA6)") (class "Default")
      (node (ref "U1") (pin "A6") (pinfunction "A6_A6") (pintype "bidirectional"))
    )
    (net (code "83") (name "unconnected-(U1-PadA7)") (class "Default")
      (node (ref "U1") (pin "A7") (pinfunction "A7_A7") (pintype "bidirectional"))
    )
    (net (code "84") (name "unconnected-(U1-PadA8)") (class "Default")
      (node (ref "U1") (pin "A8") (pinfunction "A8_A8") (pintype "bidirectional"))
    )
    (net (code "85") (name "unconnected-(U1-PadA9)") (class "Default")
      (node (ref "U1") (pin "A9") (pinfunction "A9_A9") (pintype "bidirectional"))
    )
    (net (code "86") (name "unconnected-(U1-PadA10)") (class "Default")
      (node (ref "U1") (pin "A10") (pinfunction "A10_A10") (pintype "bidirectional"))
    )
    (net (code "87") (name "unconnected-(U1-PadA11)") (class "Default")
      (node (ref "U1") (pin "A11") (pinfunction "A11_A11") (pintype "bidirectional"))
    )
    (net (code "88") (name "unconnected-(U1-PadA12)") (class "Default")
      (node (ref "U1") (pin "A12") (pinfunction "A12_A12") (pintype "bidirectional"))
    )
    (net (code "89") (name "unconnected-(U1-PadA13)") (class "Default")
      (node (ref "U1") (pin "A13") (pinfunction "A13_A13") (pintype "bidirectional"))
    )
    (net (code "90") (name "unconnected-(U1-PadA14)") (class "Default")
      (node (ref "U1") (pin "A14") (pinfunction "A14_A14") (pintype "bidirectional"))
    )
    (net (code "91") (name "unconnected-(U1-PadA15)") (class "Default")
      (node (ref "U1") (pin "A15") (pinfunction "A15_A15") (pintype "bidirectional"))
    )
    (net (code "92") (name "unconnected-(U1-PadAREF)") (class "Default")
      (node (ref "U1") (pin "AREF") (pinfunction "AREF_AREF") (pintype "bidirectional"))
    )
    (net (code "93") (name "unconnected-(U1-PadIOREF)") (class "Default")
      (node (ref "U1") (pin "IOREF") (pinfunction "IOREF_IOREF") (pintype "bidirectional"))
    )
    (net (code "94") (name "unconnected-(U1-PadRESET)") (class "Default")
      (node (ref "U1") (pin "RESET") (pinfunction "RESET_RESET") (pintype "bidirectional"))
    )
    (net (code "95") (name "unconnected-(U1-PadSCL1)") (class "Default")
      (node (ref "U1") (pin "SCL1") (pinfunction "SCL1_SCL1") (pintype "bidirectional"))
    )
    (net (code "96") (name "unconnected-(U1-PadSDA1)") (class "Default")
      (node (ref "U1") (pin "SDA1") (pinfunction "SDA1_SDA1") (pintype "bidirectional"))
    )
    (net (code "97") (name "unconnected-(U1-PadVIN)") (class "Default")
      (node (ref "U1") (pin "VIN") (pinfunction "VIN_VIN") (pintype "bidirectional"))
    )
  )
)
